# Sheet1.net
KiCad netlist of a schematic drawn in Altium Designer
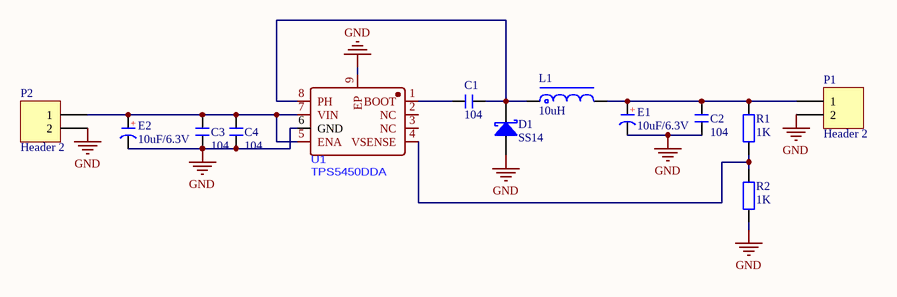
[diagram p0: Sheet1.SchDoc]

(export (version "E")
  (design (tool "Eeschema 10.0.6"))
  (components
    (comp (ref "C1")
      (value "104")
      (footprint "C 0805_L")
      (description "贴片电容")
      (libsource (lib "01 - 电容-电阻-电感") (part "C"))
    )
    (comp (ref "C2")
      (value "104")
      (footprint "C 0805_L")
      (description "贴片电容")
      (libsource (lib "01 - 电容-电阻-电感") (part "C"))
    )
    (comp (ref "C3")
      (value "104")
      (footprint "C 0805_L")
      (description "贴片电容")
      (libsource (lib "01 - 电容-电阻-电感") (part "C"))
    )
    (comp (ref "C4")
      (value "104")
      (footprint "C 0805_L")
      (description "贴片电容")
      (libsource (lib "01 - 电容-电阻-电感") (part "C"))
    )
    (comp (ref "D1")
      (value "SS14")
      (footprint "SMA")
      (description "肖特基二极管")
      (libsource (lib "02 - 二极管(LED)-三极管-整流桥") (part "SS14"))
    )
    (comp (ref "E1")
      (value "10uF/6.3V")
      (footprint "CS 2.0*5*8 - C")
      (description "直插固态电容")
      (libsource (lib "01 - 电容-电阻-电感") (part "CS"))
    )
    (comp (ref "E2")
      (value "10uF/6.3V")
      (footprint "CS 2.0*5*8 - C")
      (description "直插固态电容")
      (libsource (lib "01 - 电容-电阻-电感") (part "CS"))
    )
    (comp (ref "L1")
      (value "10uH")
      (footprint "CD31")
      (description "CD系列贴片线绕功率电感")
      (libsource (lib "01 - 电容-电阻-电感") (part "L-SMD"))
    )
    (comp (ref "P1")
      (value "Header 2")
      (footprint "HDR1X2")
      (description "Header, 2-Pin")
      (fields (field (name "PUBLISHER") "Altium Limited"))
      (libsource (lib "") (part "Header 2_1"))
    )
    (comp (ref "P2")
      (value "Header 2")
      (footprint "HDR1X2")
      (description "Header, 2-Pin")
      (fields (field (name "PUBLISHER") "Altium Limited"))
      (libsource (lib "Miscellaneous Connectors") (part "Header 2"))
    )
    (comp (ref "R1")
      (value "1K")
      (footprint "R 0805_L")
      (description "贴片电阻")
      (libsource (lib "01 - 电容-电阻-电感") (part "R"))
    )
    (comp (ref "R2")
      (value "1K")
      (footprint "R 0805_L")
      (description "贴片电阻")
      (libsource (lib "01 - 电容-电阻-电感") (part "R"))
    )
    (comp (ref "U1")
      (value "TPS5450DDA")
      (footprint "SOP-8_L4.9-W3.9-P1.27-LS6.0-TL-EP-1")
      (libsource (lib "PCB_Project") (part "TPS5450DDA"))
    )
  )
  (nets
    (net (code "1") (name "GND") (class "Default")
      (node (ref "C2") (pin "1") (pinfunction "1_1") (pintype "passive"))
      (node (ref "C3") (pin "1") (pinfunction "1_1") (pintype "passive"))
      (node (ref "C4") (pin "1") (pinfunction "1_1") (pintype "passive"))
      (node (ref "D1") (pin "1") (pinfunction "A_1") (pintype "passive"))
      (node (ref "E1") (pin "2") (pinfunction "K_2") (pintype "passive"))
      (node (ref "E2") (pin "2") (pinfunction "K_2") (pintype "passive"))
      (node (ref "P1") (pin "2") (pinfunction "2_2") (pintype "passive"))
      (node (ref "P2") (pin "2") (pinfunction "2_2") (pintype "passive"))
      (node (ref "R2") (pin "1") (pinfunction "1_1") (pintype "passive"))
      (node (ref "U1") (pin "6") (pinfunction "GND_6") (pintype "passive"))
      (node (ref "U1") (pin "9") (pinfunction "EP_9") (pintype "passive"))
    )
    (net (code "2") (name "Net-(D1-K)") (class "Default")
      (node (ref "C1") (pin "1") (pinfunction "1_1") (pintype "passive"))
      (node (ref "D1") (pin "2") (pinfunction "K_2") (pintype "passive"))
      (node (ref "L1") (pin "1") (pinfunction "1_1") (pintype "passive"))
      (node (ref "U1") (pin "8") (pinfunction "PH_8") (pintype "passive"))
    )
    (net (code "3") (name "Net-(E1-A)") (class "Default")
      (node (ref "C2") (pin "2") (pinfunction "2_2") (pintype "passive"))
      (node (ref "E1") (pin "1") (pinfunction "A_1") (pintype "passive"))
      (node (ref "L1") (pin "2") (pinfunction "2_2") (pintype "passive"))
      (node (ref "P1") (pin "1") (pinfunction "1_1") (pintype "passive"))
      (node (ref "R1") (pin "2") (pinfunction "2_2") (pintype "passive"))
    )
    (net (code "4") (name "Net-(E2-A)") (class "Default")
      (node (ref "C3") (pin "2") (pinfunction "2_2") (pintype "passive"))
      (node (ref "C4") (pin "2") (pinfunction "2_2") (pintype "passive"))
      (node (ref "E2") (pin "1") (pinfunction "A_1") (pintype "passive"))
      (node (ref "P2") (pin "1") (pinfunction "1_1") (pintype "passive"))
      (node (ref "U1") (pin "5") (pinfunction "ENA_5") (pintype "passive"))
      (node (ref "U1") (pin "7") (pinfunction "VIN_7") (pintype "passive"))
    )
    (net (code "5") (name "Net-(U1-BOOT)") (class "Default")
      (node (ref "C1") (pin "2") (pinfunction "2_2") (pintype "passive"))
      (node (ref "U1") (pin "1") (pinfunction "BOOT_1") (pintype "passive"))
    )
    (net (code "6") (name "Net-(U1-VSENSE)") (class "Default")
      (node (ref "R1") (pin "1") (pinfunction "1_1") (pintype "passive"))
      (node (ref "R2") (pin "2") (pinfunction "2_2") (pintype "passive"))
      (node (ref "U1") (pin "4") (pinfunction "VSENSE_4") (pintype "passive"))
    )
    (net (code "7") (name "unconnected-(U1-NC-Pad2)") (class "Default")
      (node (ref "U1") (pin "2") (pinfunction "NC_2") (pintype "passive"))
    )
    (net (code "8") (name "unconnected-(U1-NC-Pad3)") (class "Default")
      (node (ref "U1") (pin "3") (pinfunction "NC_3") (pintype "passive"))
    )
  )
)
